# SPI.net
KiCad netlist of a schematic drawn in Altium Designer
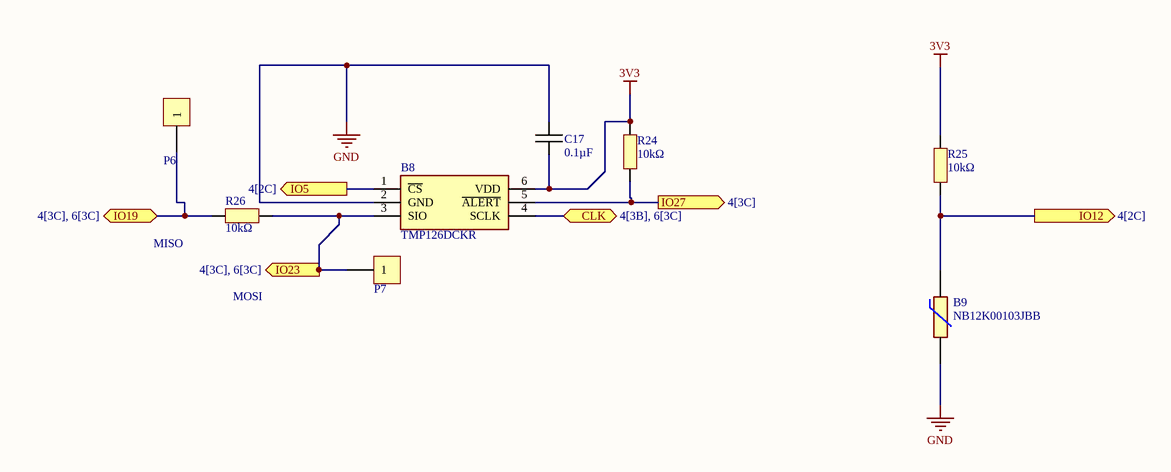
[diagram p0: SPI.SchDoc]

(export (version "E")
  (design (tool "Eeschema 10.0.6"))
  (components
    (comp (ref "B8")
      (value "TMP126DCKR")
      (footprint "SOT65P210X110-6N")
      (fields (field (name "MOUSER PART NUMBER") "595-TMP126DCKR"))
      (libsource (lib "SCHLibrary") (part "TMP126DCKR"))
    )
    (comp (ref "B9")
      (value "NB12K00103JBB")
      (footprint "RESC2212X50N")
      (description "NTC SMD Thermistor, NB12K, 10K, 5% AVX 10k 0805 Protection NTC Thermistor, 5s, 2 x 1.25 x 1.3mm")
      (fields (field (name "MOUSER PART NUMBER") "581-NB12K00103JBB"))
      (libsource (lib "SCHLibrary") (part "NB12K00103JBB"))
    )
    (comp (ref "C17")
      (value "0.1µF")
      (footprint "CAPC1005X06N")
      (libsource (lib "SCHLibrary") (part "Capacitor"))
    )
    (comp (ref "P6")
      (value "Plage CMS 10x5")
      (footprint "Plage CMS 10x5")
      (description "Plage de report CMS 10x5mm")
      (libsource (lib "") (part "Plage CMS 10x5_1"))
    )
    (comp (ref "P7")
      (value "Plage CMS 10x5")
      (footprint "Plage CMS 10x5")
      (description "Plage de report CMS 10x5mm")
      (libsource (lib "SCHLibrary") (part "Plage CMS 10x5"))
    )
    (comp (ref "R24")
      (value "10kΩ")
      (footprint "RESC1005X06N")
      (libsource (lib "SCHLibrary") (part "Resistor"))
    )
    (comp (ref "R25") (value "10kΩ") (footprint "RESC1005X06N") (libsource (lib "") (part "Resistor_1")))
    (comp (ref "R26") (value "10kΩ") (footprint "RESC1005X06N") (libsource (lib "") (part "Resistor_2")))
  )
  (nets
    (net (code "1") (name "/CLK") (class "Default")
      (node (ref "B8") (pin "4") (pinfunction "SCLK_4") (pintype "passive"))
    )
    (net (code "2") (name "/IO5") (class "Default")
      (node (ref "B8") (pin "1") (pinfunction "~{CS}_1") (pintype "passive"))
    )
    (net (code "3") (name "/IO12") (class "Default")
      (node (ref "B9") (pin "1") (pinfunction "1_1") (pintype "passive"))
      (node (ref "R25") (pin "2") (pinfunction "2_2") (pintype "passive"))
    )
    (net (code "4") (name "/IO19") (class "Default")
      (node (ref "P6") (pin "1") (pinfunction "1_1") (pintype "passive"))
      (node (ref "R26") (pin "2") (pinfunction "2_2") (pintype "passive"))
    )
    (net (code "5") (name "/IO23") (class "Default")
      (node (ref "B8") (pin "3") (pinfunction "SIO_3") (pintype "passive"))
      (node (ref "P7") (pin "1") (pinfunction "1_1") (pintype "passive"))
      (node (ref "R26") (pin "1") (pinfunction "1_1") (pintype "passive"))
    )
    (net (code "6") (name "/IO27") (class "Default")
      (node (ref "B8") (pin "5") (pinfunction "~{ALERT}_5") (pintype "passive"))
      (node (ref "R24") (pin "1") (pinfunction "1_1") (pintype "passive"))
    )
    (net (code "7") (name "3V3") (class "Default")
      (node (ref "B8") (pin "6") (pinfunction "VDD_6") (pintype "passive"))
      (node (ref "C17") (pin "1") (pinfunction "1_1") (pintype "passive"))
      (node (ref "R24") (pin "2") (pinfunction "2_2") (pintype "passive"))
      (node (ref "R25") (pin "1") (pinfunction "1_1") (pintype "passive"))
    )
    (net (code "8") (name "GND") (class "Default")
      (node (ref "B8") (pin "2") (pinfunction "GND_2") (pintype "passive"))
      (node (ref "B9") (pin "2") (pinfunction "2_2") (pintype "passive"))
      (node (ref "C17") (pin "2") (pinfunction "2_2") (pintype "passive"))
    )
  )
)
